# untitled.net
KiCad netlist of a schematic drawn in EAGLE
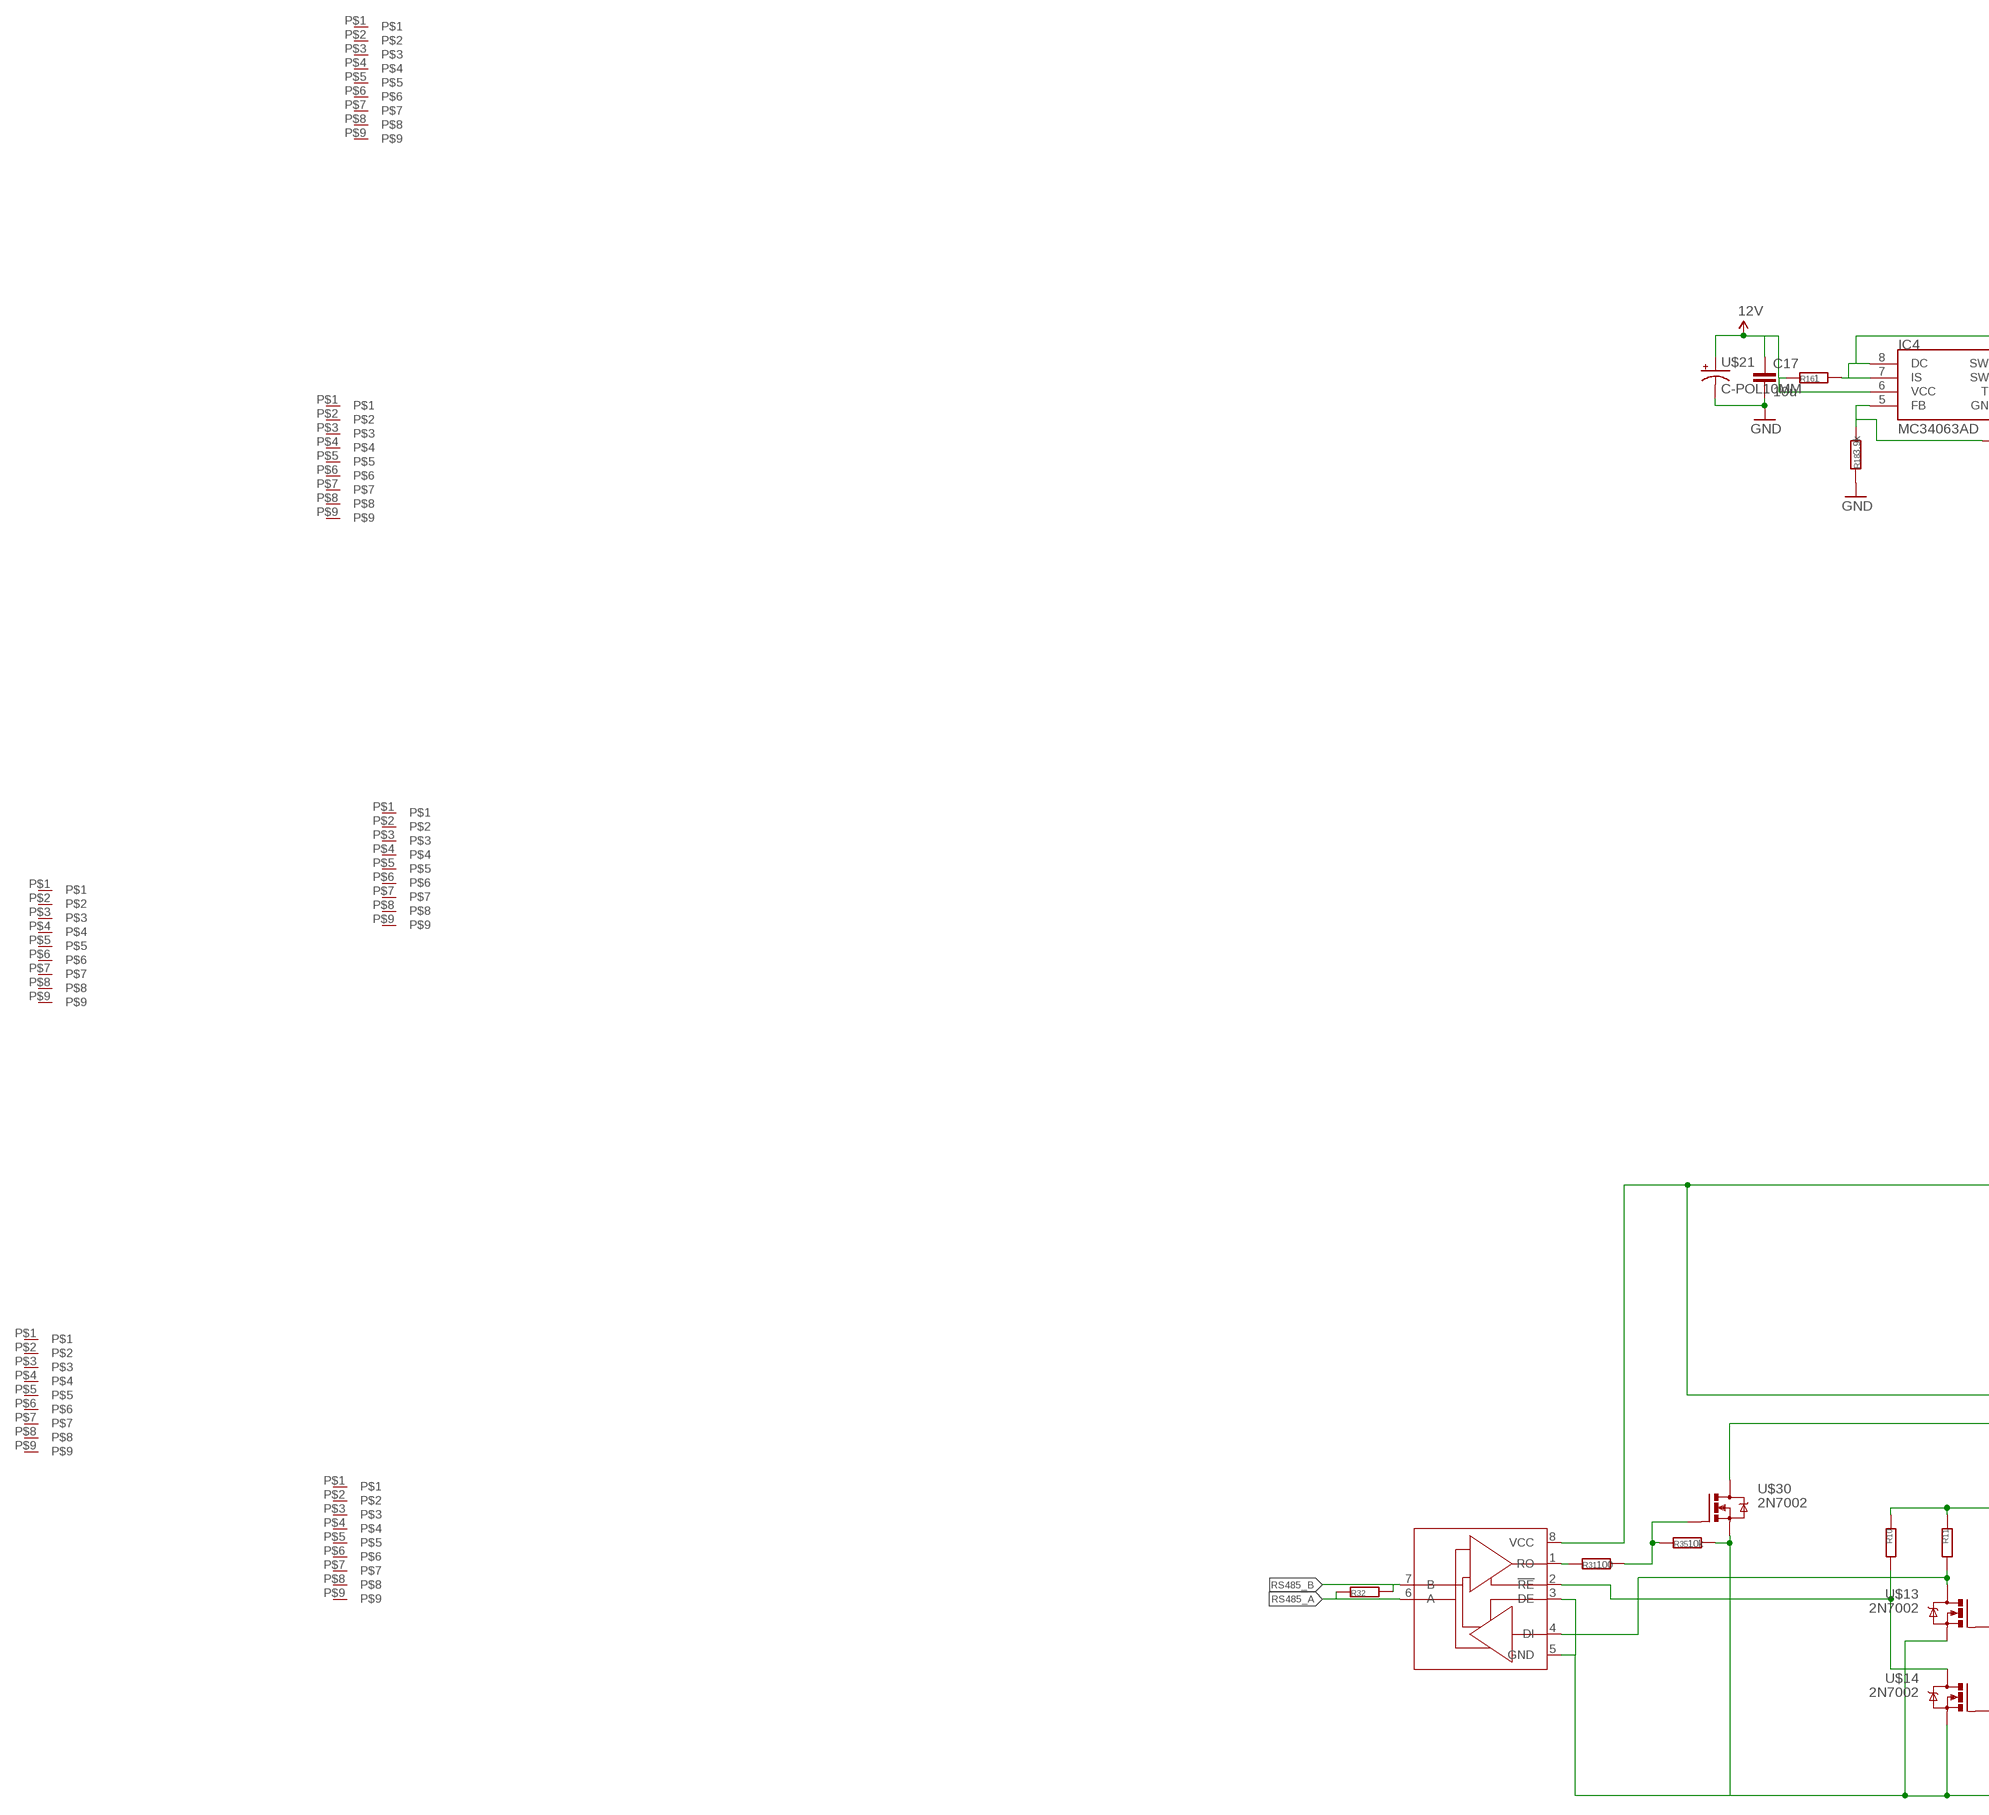
[diagram p0: schematic, sheet 1, part 1 of 2]
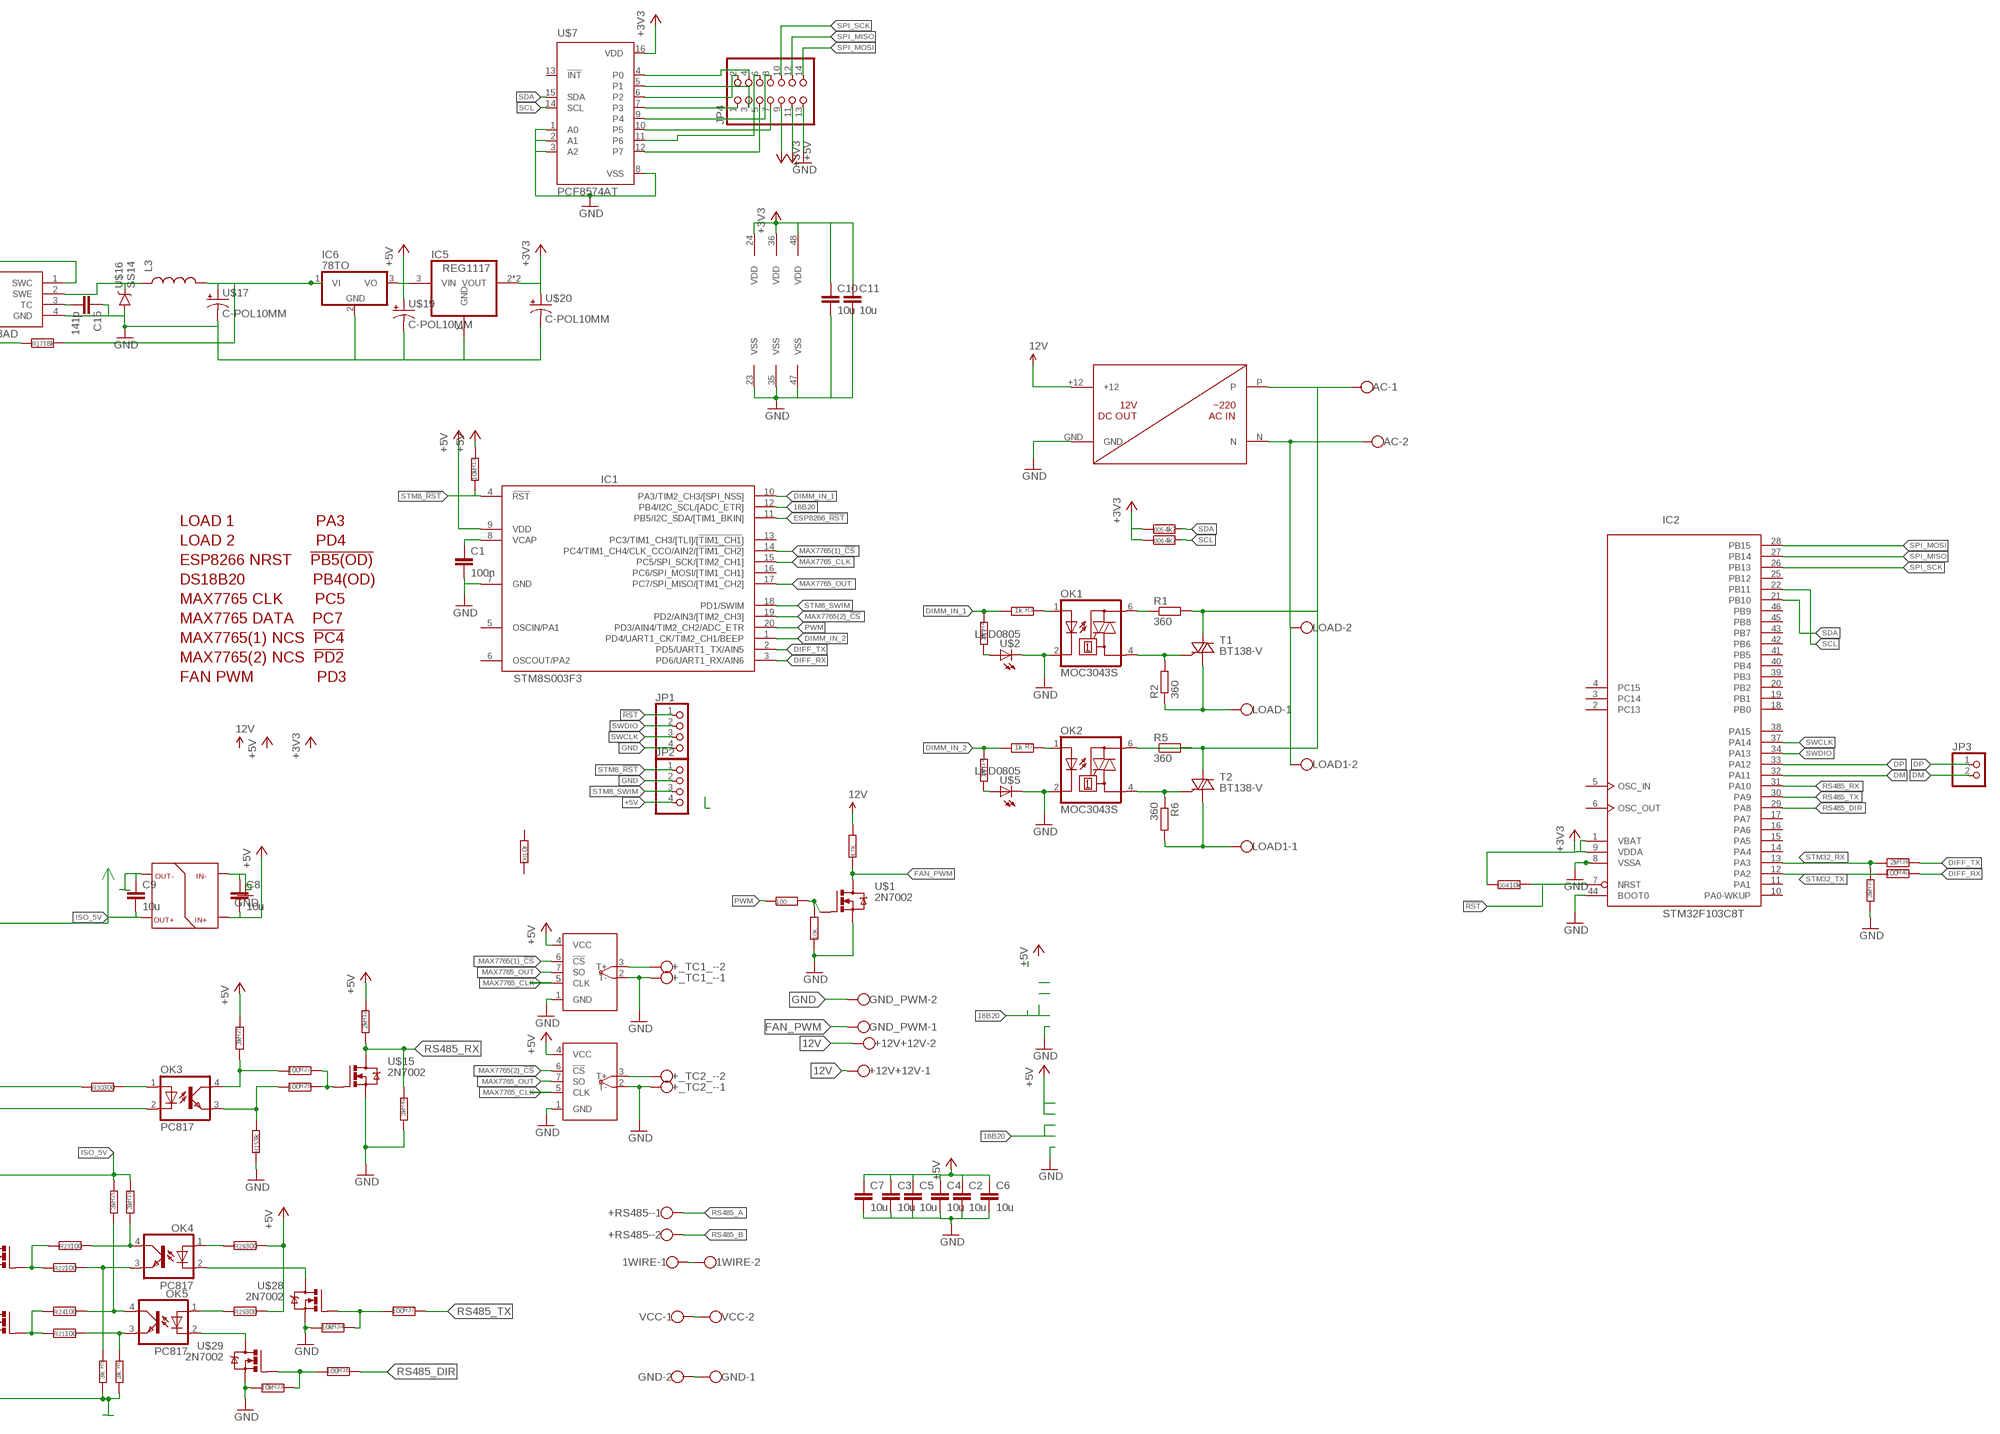
[diagram p1: schematic, sheet 1, part 2 of 2]
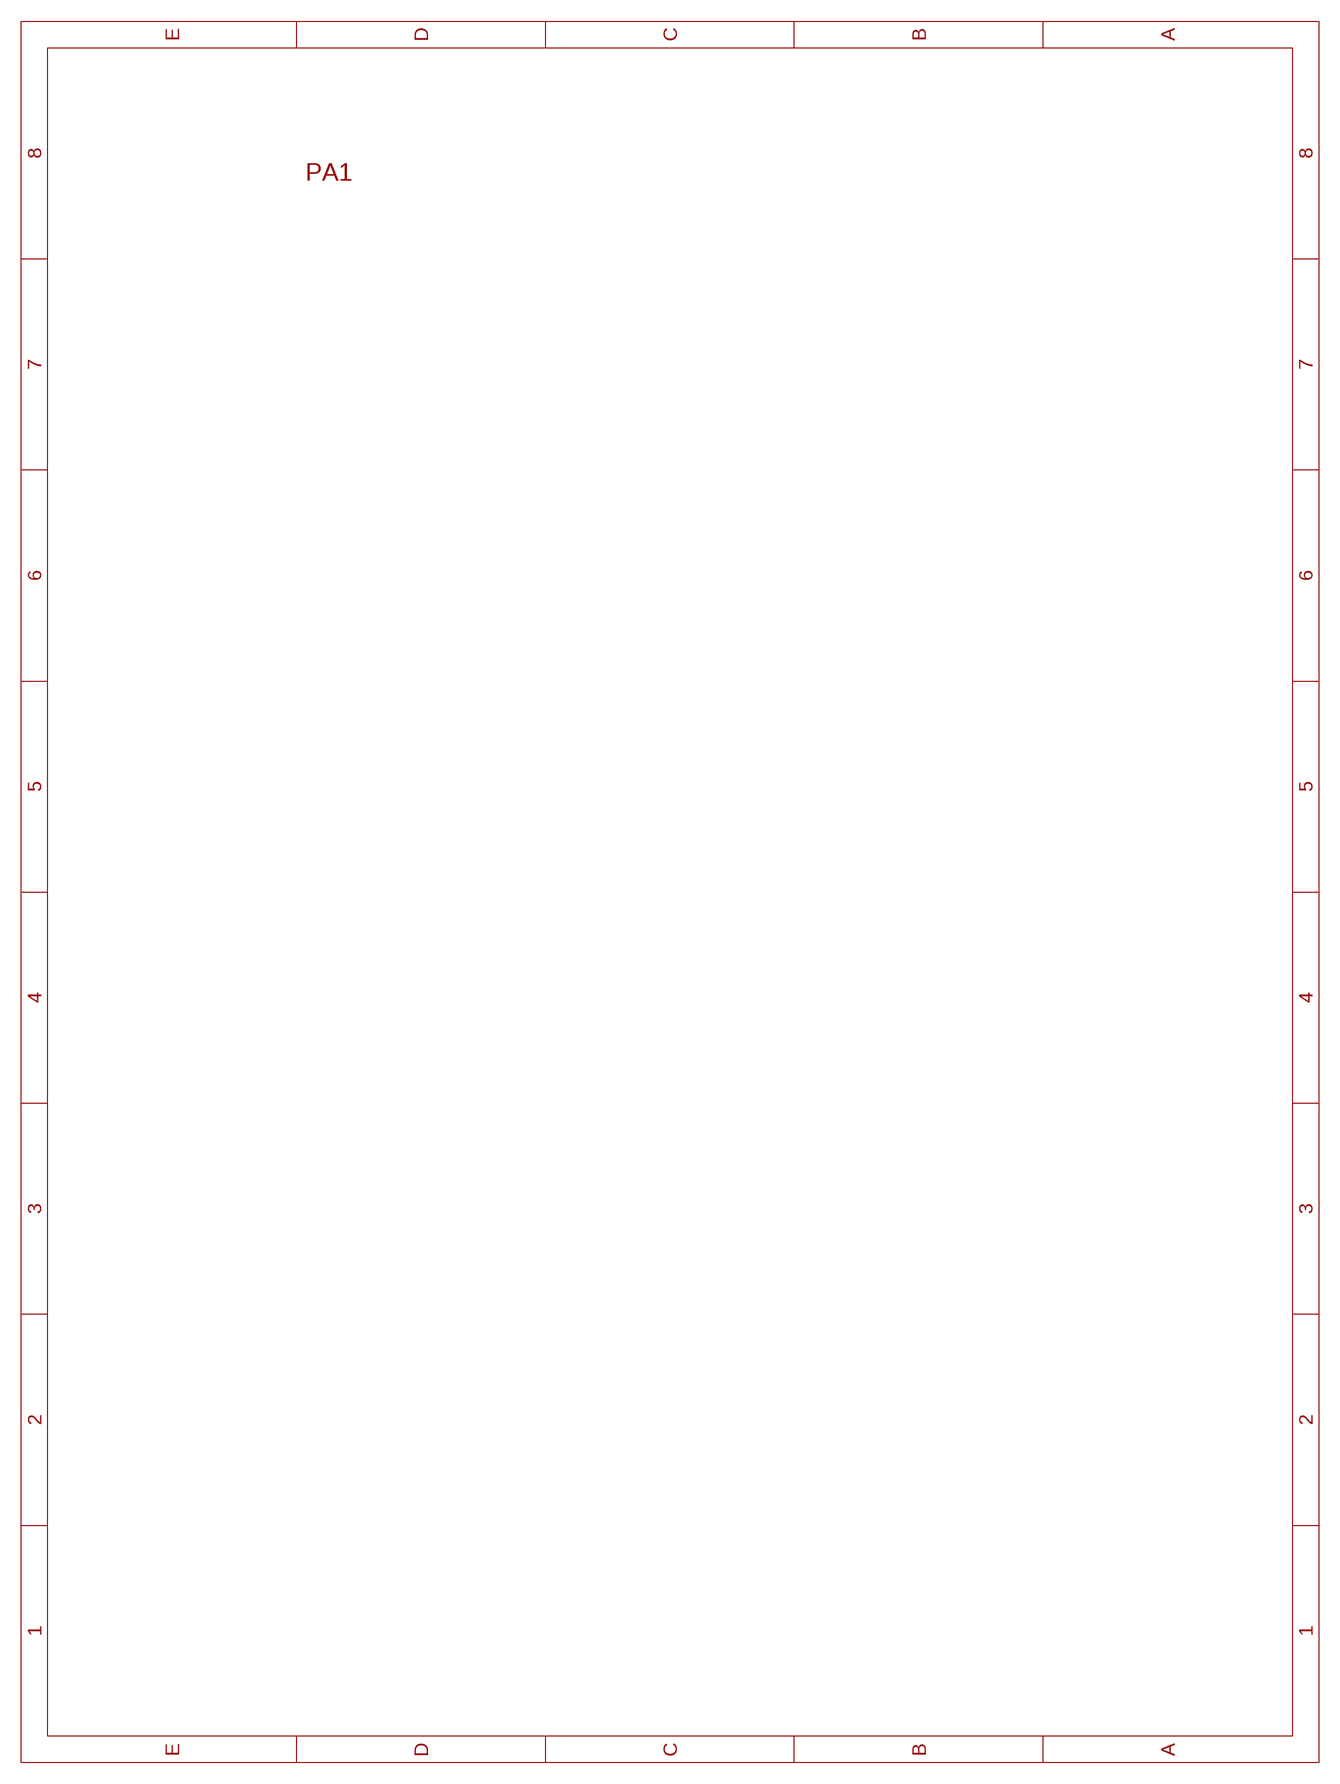
[diagram p2: schematic, sheet 2]

(export (version "E")
  (design (tool "Eeschema 10.0.6"))
  (components
    (comp (ref "+12V+12V")
      (value "W237-102")
      (footprint "eagle-import:W237-102")
      (fields (field (name "MPN") "237-102"))
      (libsource (lib "eagle-import") (part "W237-102"))
    )
    (comp (ref "+RS485-")
      (value "W237-102")
      (footprint "eagle-import:W237-102")
      (fields (field (name "MPN") "237-102"))
      (libsource (lib "eagle-import") (part "W237-102"))
    )
    (comp (ref "+_TC1_-")
      (value "W237-102")
      (footprint "eagle-import:W237-102")
      (fields (field (name "MPN") "237-102"))
      (libsource (lib "eagle-import") (part "W237-102"))
    )
    (comp (ref "+_TC2_-")
      (value "W237-102")
      (footprint "eagle-import:W237-102")
      (fields (field (name "MPN") "237-102"))
      (libsource (lib "eagle-import") (part "W237-102"))
    )
    (comp (ref "001")
      (value "0r")
      (footprint "eagle-import:0603")
      (libsource (lib "eagle-import") (part "R0603"))
    )
    (comp (ref "1WIRE")
      (value "W237-102")
      (footprint "eagle-import:W237-102")
      (fields (field (name "MPN") "237-102"))
      (libsource (lib "eagle-import") (part "W237-102"))
    )
    (comp (ref "004")
      (value "10k")
      (footprint "eagle-import:0603")
      (libsource (lib "eagle-import") (part "R0603"))
    )
    (comp (ref "4.7K")
      (value "R0603")
      (footprint "eagle-import:0603")
      (libsource (lib "eagle-import") (part "R0603"))
    )
    (comp (ref "005")
      (value "4k7")
      (footprint "eagle-import:0603")
      (libsource (lib "eagle-import") (part "R0603"))
    )
    (comp (ref "006")
      (value "4k7")
      (footprint "eagle-import:0603")
      (libsource (lib "eagle-import") (part "R0603"))
    )
    (comp (ref "10K")
      (value "R0603")
      (footprint "eagle-import:0603")
      (libsource (lib "eagle-import") (part "R0603"))
    )
    (comp (ref "100")
      (value "R0603")
      (footprint "eagle-import:0603")
      (libsource (lib "eagle-import") (part "R0603"))
    )
    (comp (ref "AC")
      (value "W237-102")
      (footprint "eagle-import:W237-102")
      (fields (field (name "MPN") "237-102"))
      (libsource (lib "eagle-import") (part "W237-102"))
    )
    (comp (ref "C1")
      (value "100n")
      (footprint "eagle-import:C0603")
      (libsource (lib "eagle-import") (part "CC0603"))
    )
    (comp (ref "C2")
      (value "10u")
      (footprint "eagle-import:C0805")
      (libsource (lib "eagle-import") (part "CC0805"))
    )
    (comp (ref "C3")
      (value "10u")
      (footprint "eagle-import:C0805")
      (libsource (lib "eagle-import") (part "CC0805"))
    )
    (comp (ref "C4")
      (value "10u")
      (footprint "eagle-import:C0805")
      (libsource (lib "eagle-import") (part "CC0805"))
    )
    (comp (ref "C5")
      (value "10u")
      (footprint "eagle-import:C0805")
      (libsource (lib "eagle-import") (part "CC0805"))
    )
    (comp (ref "C6")
      (value "10u")
      (footprint "eagle-import:C0805")
      (libsource (lib "eagle-import") (part "CC0805"))
    )
    (comp (ref "C7")
      (value "10u")
      (footprint "eagle-import:C0805")
      (libsource (lib "eagle-import") (part "CC0805"))
    )
    (comp (ref "C8")
      (value "10u")
      (footprint "eagle-import:C0805")
      (libsource (lib "eagle-import") (part "CC0805"))
    )
    (comp (ref "C9")
      (value "10u")
      (footprint "eagle-import:C0805")
      (libsource (lib "eagle-import") (part "CC0805"))
    )
    (comp (ref "C10")
      (value "10u")
      (footprint "eagle-import:C0603")
      (libsource (lib "eagle-import") (part "CC0603"))
    )
    (comp (ref "C11")
      (value "10u")
      (footprint "eagle-import:C0603")
      (libsource (lib "eagle-import") (part "CC0603"))
    )
    (comp (ref "C15")
      (value "141p")
      (footprint "eagle-import:C0603")
      (libsource (lib "eagle-import") (part "CC0603"))
    )
    (comp (ref "C17")
      (value "10u")
      (footprint "eagle-import:C0805")
      (libsource (lib "eagle-import") (part "CC0805"))
    )
    (comp (ref "GND")
      (value "W237-102")
      (footprint "eagle-import:W237-102")
      (fields (field (name "MPN") "237-102"))
      (libsource (lib "eagle-import") (part "W237-102"))
    )
    (comp (ref "GND_PWM")
      (value "W237-102")
      (footprint "eagle-import:W237-102")
      (fields (field (name "MPN") "237-102"))
      (libsource (lib "eagle-import") (part "W237-102"))
    )
    (comp (ref "IC1")
      (value "STM8S003F3")
      (footprint "eagle-import:TSSOP20")
      (libsource (lib "eagle-import") (part "STM8S003F3"))
    )
    (comp (ref "IC2")
      (value "STM32F103C8T")
      (footprint "eagle-import:LQFP48")
      (libsource (lib "eagle-import") (part "STM32F103CT8"))
    )
    (comp (ref "IC4")
      (value "MC34063AD")
      (footprint "eagle-import:SOIC8")
      (libsource (lib "eagle-import") (part "MC34063AD"))
    )
    (comp (ref "IC5")
      (value "REG1117")
      (footprint "eagle-import:SOT223")
      (libsource (lib "eagle-import") (part "REG1117"))
    )
    (comp (ref "IC6")
      (value "78TO")
      (footprint "eagle-import:D2PACK")
      (libsource (lib "eagle-import") (part "78TO"))
    )
    (comp (ref "JP1")
      (value "PINHD-1X4")
      (footprint "eagle-import:1X04")
      (libsource (lib "eagle-import") (part "PINHD-1X4"))
    )
    (comp (ref "JP2")
      (value "PINHD-1X4")
      (footprint "eagle-import:1X04")
      (libsource (lib "eagle-import") (part "PINHD-1X4"))
    )
    (comp (ref "JP3")
      (value "PINHD-1X02_2.00")
      (footprint "eagle-import:1X02M")
      (libsource (lib "eagle-import") (part "PINHD-1X02_2.00"))
    )
    (comp (ref "JP4")
      (value "PINHD-2X07_2.54-SMD")
      (footprint "eagle-import:2X07SMD")
      (libsource (lib "eagle-import") (part "PINHD-2X07_2.54-SMD"))
    )
    (comp (ref "L3")
      (value "INDUCTORSRU1038")
      (footprint "eagle-import:SRU1038")
      (libsource (lib "eagle-import") (part "INDUCTORSRU1038"))
    )
    (comp (ref "LOAD")
      (value "W237-102")
      (footprint "eagle-import:W237-102")
      (fields (field (name "MPN") "237-102"))
      (libsource (lib "eagle-import") (part "W237-102"))
    )
    (comp (ref "LOAD1")
      (value "W237-102")
      (footprint "eagle-import:W237-102")
      (fields (field (name "MPN") "237-102"))
      (libsource (lib "eagle-import") (part "W237-102"))
    )
    (comp (ref "OK1")
      (value "MOC3043S")
      (footprint "eagle-import:DIL6-SMD")
      (fields (field (name "MF") "FAIRCHILD SEMICONDUCTOR") (field (name "MPN") "MOC3043SM"))
      (libsource (lib "eagle-import") (part "MOC30S43"))
    )
    (comp (ref "OK2")
      (value "MOC3043S")
      (footprint "eagle-import:DIL6-SMD")
      (fields (field (name "MF") "FAIRCHILD SEMICONDUCTOR") (field (name "MPN") "MOC3043SM"))
      (libsource (lib "eagle-import") (part "MOC30S43"))
    )
    (comp (ref "OK3")
      (value "PC817")
      (footprint "eagle-import:DIL4-SMD")
      (libsource (lib "eagle-import") (part "PC817"))
    )
    (comp (ref "OK4")
      (value "PC817")
      (footprint "eagle-import:DIL4-SMD")
      (libsource (lib "eagle-import") (part "PC817"))
    )
    (comp (ref "OK5")
      (value "PC817")
      (footprint "eagle-import:DIL4-SMD")
      (libsource (lib "eagle-import") (part "PC817"))
    )
    (comp (ref "R1")
      (value "360")
      (footprint "eagle-import:0207_5V")
      (libsource (lib "eagle-import") (part "R-EU_0207/5V"))
    )
    (comp (ref "R2")
      (value "360")
      (footprint "eagle-import:0207_5V")
      (libsource (lib "eagle-import") (part "R-EU_0207/5V"))
    )
    (comp (ref "R3")
      (value "1k")
      (footprint "eagle-import:0603")
      (libsource (lib "eagle-import") (part "R0603"))
    )
    (comp (ref "R4")
      (value "1k")
      (footprint "eagle-import:0603")
      (libsource (lib "eagle-import") (part "R0603"))
    )
    (comp (ref "R5")
      (value "360")
      (footprint "eagle-import:0207_5V")
      (libsource (lib "eagle-import") (part "R-EU_0207/5V"))
    )
    (comp (ref "R6")
      (value "360")
      (footprint "eagle-import:0207_5V")
      (libsource (lib "eagle-import") (part "R-EU_0207/5V"))
    )
    (comp (ref "R7")
      (value "1k")
      (footprint "eagle-import:0603")
      (libsource (lib "eagle-import") (part "R0603"))
    )
    (comp (ref "R8")
      (value "3k")
      (footprint "eagle-import:0603")
      (libsource (lib "eagle-import") (part "R0603"))
    )
    (comp (ref "R9")
      (value "3k")
      (footprint "eagle-import:0603")
      (libsource (lib "eagle-import") (part "R0603"))
    )
    (comp (ref "R10")
      (value "R0603")
      (footprint "eagle-import:0603")
      (libsource (lib "eagle-import") (part "R0603"))
    )
    (comp (ref "R11")
      (value "R0603")
      (footprint "eagle-import:0603")
      (libsource (lib "eagle-import") (part "R0603"))
    )
    (comp (ref "R12")
      (value "2k")
      (footprint "eagle-import:0603")
      (libsource (lib "eagle-import") (part "R0603"))
    )
    (comp (ref "R13")
      (value "10k")
      (footprint "eagle-import:0603")
      (libsource (lib "eagle-import") (part "R0603"))
    )
    (comp (ref "R14")
      (value "1k")
      (footprint "eagle-import:0603")
      (libsource (lib "eagle-import") (part "R0603"))
    )
    (comp (ref "R15")
      (value "3k")
      (footprint "eagle-import:0603")
      (libsource (lib "eagle-import") (part "R0603"))
    )
    (comp (ref "R16")
      (value "1")
      (footprint "eagle-import:R0805")
      (libsource (lib "eagle-import") (part "R0805"))
    )
    (comp (ref "R17")
      (value "18k")
      (footprint "eagle-import:0603")
      (libsource (lib "eagle-import") (part "R0603"))
    )
    (comp (ref "R18")
      (value "3.9k")
      (footprint "eagle-import:0603")
      (libsource (lib "eagle-import") (part "R0603"))
    )
    (comp (ref "R19")
      (value "3k")
      (footprint "eagle-import:0603")
      (libsource (lib "eagle-import") (part "R0603"))
    )
    (comp (ref "R20")
      (value "3k")
      (footprint "eagle-import:0603")
      (libsource (lib "eagle-import") (part "R0603"))
    )
    (comp (ref "R21")
      (value "100")
      (footprint "eagle-import:0603")
      (libsource (lib "eagle-import") (part "R0603"))
    )
    (comp (ref "R22")
      (value "100")
      (footprint "eagle-import:0603")
      (libsource (lib "eagle-import") (part "R0603"))
    )
    (comp (ref "R23")
      (value "100")
      (footprint "eagle-import:0603")
      (libsource (lib "eagle-import") (part "R0603"))
    )
    (comp (ref "R24")
      (value "100")
      (footprint "eagle-import:0603")
      (libsource (lib "eagle-import") (part "R0603"))
    )
    (comp (ref "R25")
      (value "3k")
      (footprint "eagle-import:0603")
      (libsource (lib "eagle-import") (part "R0603"))
    )
    (comp (ref "R26")
      (value "100")
      (footprint "eagle-import:0603")
      (libsource (lib "eagle-import") (part "R0603"))
    )
    (comp (ref "R27")
      (value "100")
      (footprint "eagle-import:0603")
      (libsource (lib "eagle-import") (part "R0603"))
    )
    (comp (ref "R28")
      (value "300")
      (footprint "eagle-import:0603")
      (libsource (lib "eagle-import") (part "R0603"))
    )
    (comp (ref "R29")
      (value "300")
      (footprint "eagle-import:0603")
      (libsource (lib "eagle-import") (part "R0603"))
    )
    (comp (ref "R30")
      (value "300")
      (footprint "eagle-import:0603")
      (libsource (lib "eagle-import") (part "R0603"))
    )
    (comp (ref "R31")
      (value "100")
      (footprint "eagle-import:0603")
      (libsource (lib "eagle-import") (part "R0603"))
    )
    (comp (ref "R32")
      (value "R0805")
      (footprint "eagle-import:R0805")
      (libsource (lib "eagle-import") (part "R0805"))
    )
    (comp (ref "R33")
      (value "10k")
      (footprint "eagle-import:0603")
      (libsource (lib "eagle-import") (part "R0603"))
    )
    (comp (ref "R34")
      (value "10k")
      (footprint "eagle-import:0603")
      (libsource (lib "eagle-import") (part "R0603"))
    )
    (comp (ref "R35")
      (value "10k")
      (footprint "eagle-import:0603")
      (libsource (lib "eagle-import") (part "R0603"))
    )
    (comp (ref "R36")
      (value "100")
      (footprint "eagle-import:0603")
      (libsource (lib "eagle-import") (part "R0603"))
    )
    (comp (ref "R37")
      (value "100")
      (footprint "eagle-import:0603")
      (libsource (lib "eagle-import") (part "R0603"))
    )
    (comp (ref "R38")
      (value "2k")
      (footprint "eagle-import:0603")
      (libsource (lib "eagle-import") (part "R0603"))
    )
    (comp (ref "R39")
      (value "3k")
      (footprint "eagle-import:0603")
      (libsource (lib "eagle-import") (part "R0603"))
    )
    (comp (ref "R40")
      (value "100")
      (footprint "eagle-import:0603")
      (libsource (lib "eagle-import") (part "R0603"))
    )
    (comp (ref "R41")
      (value "3k")
      (footprint "eagle-import:0603")
      (libsource (lib "eagle-import") (part "R0603"))
    )
    (comp (ref "T1")
      (value "BT138-V")
      (footprint "eagle-import:TO220BV")
      (libsource (lib "eagle-import") (part "BT138-V"))
    )
    (comp (ref "T2")
      (value "BT138-V")
      (footprint "eagle-import:TO220BV")
      (libsource (lib "eagle-import") (part "BT138-V"))
    )
    (comp (ref "U$1")
      (value "2N7002")
      (footprint "eagle-import:SOT23")
      (libsource (lib "eagle-import") (part "2N7002"))
    )
    (comp (ref "U$2")
      (value "LED0805")
      (footprint "eagle-import:0805-LED")
      (libsource (lib "eagle-import") (part "LED0805"))
    )
    (comp (ref "U$3")
      (value "MAX6675")
      (footprint "eagle-import:SO08")
      (libsource (lib "eagle-import") (part "MAX6675"))
    )
    (comp (ref "U$4")
      (value "ADM1485")
      (footprint "eagle-import:SO08")
      (libsource (lib "eagle-import") (part "ADM1485"))
    )
    (comp (ref "U$5")
      (value "LED0805")
      (footprint "eagle-import:0805-LED")
      (libsource (lib "eagle-import") (part "LED0805"))
    )
    (comp (ref "U$6")
      (value "MAX6675")
      (footprint "eagle-import:SO08")
      (libsource (lib "eagle-import") (part "MAX6675"))
    )
    (comp (ref "U$7")
      (value "PCF8574AT")
      (footprint "eagle-import:SO16L")
      (libsource (lib "eagle-import") (part "PCF8574AT"))
    )
    (comp (ref "U$8")
      (value "AC-DC")
      (footprint "eagle-import:ACDC12(1)")
      (libsource (lib "eagle-import") (part "AC-DC"))
    )
    (comp (ref "U$12")
      (value "DCDC5050")
      (footprint "eagle-import:DCDC_0505")
      (libsource (lib "eagle-import") (part "DCDC5050"))
    )
    (comp (ref "U$13")
      (value "2N7002")
      (footprint "eagle-import:SOT23")
      (libsource (lib "eagle-import") (part "2N7002"))
    )
    (comp (ref "U$14")
      (value "2N7002")
      (footprint "eagle-import:SOT23")
      (libsource (lib "eagle-import") (part "2N7002"))
    )
    (comp (ref "U$15")
      (value "2N7002")
      (footprint "eagle-import:SOT23")
      (libsource (lib "eagle-import") (part "2N7002"))
    )
    (comp (ref "U$16")
      (value "SS14")
      (footprint "eagle-import:SMA-DIODE")
      (libsource (lib "eagle-import") (part "SS14"))
    )
    (comp (ref "U$17")
      (value "C-POL10MM")
      (footprint "eagle-import:PCAP10")
      (libsource (lib "eagle-import") (part "C-POL10MM"))
    )
    (comp (ref "U$19")
      (value "C-POL10MM")
      (footprint "eagle-import:PCAP10")
      (libsource (lib "eagle-import") (part "C-POL10MM"))
    )
    (comp (ref "U$20")
      (value "C-POL10MM")
      (footprint "eagle-import:PCAP10")
      (libsource (lib "eagle-import") (part "C-POL10MM"))
    )
    (comp (ref "U$21")
      (value "C-POL10MM")
      (footprint "eagle-import:PCAP10")
      (libsource (lib "eagle-import") (part "C-POL10MM"))
    )
    (comp (ref "U$22")
      (value "D9MG")
      (footprint "eagle-import:D9MG")
      (libsource (lib "eagle-import") (part "D9MG"))
    )
    (comp (ref "U$23")
      (value "D9MG")
      (footprint "eagle-import:D9MG")
      (libsource (lib "eagle-import") (part "D9MG"))
    )
    (comp (ref "U$24")
      (value "D9MG")
      (footprint "eagle-import:D9MG")
      (libsource (lib "eagle-import") (part "D9MG"))
    )
    (comp (ref "U$25")
      (value "D9MG")
      (footprint "eagle-import:D9MG")
      (libsource (lib "eagle-import") (part "D9MG"))
    )
    (comp (ref "U$26")
      (value "D9MG")
      (footprint "eagle-import:D9MG")
      (libsource (lib "eagle-import") (part "D9MG"))
    )
    (comp (ref "U$27")
      (value "D9MG")
      (footprint "eagle-import:D9MG")
      (libsource (lib "eagle-import") (part "D9MG"))
    )
    (comp (ref "U$28")
      (value "2N7002")
      (footprint "eagle-import:SOT23")
      (libsource (lib "eagle-import") (part "2N7002"))
    )
    (comp (ref "U$29")
      (value "2N7002")
      (footprint "eagle-import:SOT23")
      (libsource (lib "eagle-import") (part "2N7002"))
    )
    (comp (ref "U$30")
      (value "2N7002")
      (footprint "eagle-import:SOT23")
      (libsource (lib "eagle-import") (part "2N7002"))
    )
    (comp (ref "VCC")
      (value "W237-102")
      (footprint "eagle-import:W237-102")
      (fields (field (name "MPN") "237-102"))
      (libsource (lib "eagle-import") (part "W237-102"))
    )
  )
  (nets
    (net (code "1") (name "+3V3") (class "Default")
      (node (ref "004") (pin "1") (pinfunction "1_1") (pintype "passive"))
      (node (ref "005") (pin "1") (pinfunction "1_1") (pintype "passive"))
      (node (ref "006") (pin "1") (pinfunction "1_1") (pintype "passive"))
      (node (ref "C10") (pin "1") (pinfunction "1_1") (pintype "passive"))
      (node (ref "C11") (pin "1") (pinfunction "1_1") (pintype "passive"))
      (node (ref "IC2") (pin "1") (pinfunction "VBAT_1") (pintype "power_in"))
      (node (ref "IC2") (pin "24") (pinfunction "VDD_24") (pintype "power_in"))
      (node (ref "IC2") (pin "36") (pinfunction "VDD_36") (pintype "power_in"))
      (node (ref "IC2") (pin "48") (pinfunction "VDD_48") (pintype "power_in"))
      (node (ref "IC2") (pin "9") (pinfunction "VDDA_9") (pintype "power_in"))
      (node (ref "IC5") (pin "2") (pinfunction "VOUT_2") (pintype "output"))
      (node (ref "IC5") (pin "4") (pinfunction "VOUT_4") (pintype "output"))
      (node (ref "JP4") (pin "9") (pinfunction "9_9") (pintype "passive"))
      (node (ref "U$20") (pin "P$1") (pinfunction "+_P$1") (pintype "passive"))
      (node (ref "U$7") (pin "16") (pinfunction "VDD_16") (pintype "power_in"))
    )
    (net (code "2") (name "+5V") (class "Default")
      (node (ref "C2") (pin "1") (pinfunction "1_1") (pintype "passive"))
      (node (ref "C3") (pin "1") (pinfunction "1_1") (pintype "passive"))
      (node (ref "C4") (pin "1") (pinfunction "1_1") (pintype "passive"))
      (node (ref "C5") (pin "1") (pinfunction "1_1") (pintype "passive"))
      (node (ref "C6") (pin "1") (pinfunction "1_1") (pintype "passive"))
      (node (ref "C7") (pin "1") (pinfunction "1_1") (pintype "passive"))
      (node (ref "C8") (pin "2") (pinfunction "2_2") (pintype "passive"))
      (node (ref "IC1") (pin "9") (pinfunction "VDD_9") (pintype "power_in"))
      (node (ref "IC5") (pin "3") (pinfunction "VIN_3") (pintype "input"))
      (node (ref "IC6") (pin "3") (pinfunction "VO_3") (pintype "passive"))
      (node (ref "JP2") (pin "4") (pinfunction "4_4") (pintype "passive"))
      (node (ref "JP4") (pin "11") (pinfunction "11_11") (pintype "passive"))
      (node (ref "R12") (pin "1") (pinfunction "1_1") (pintype "passive"))
      (node (ref "R13") (pin "1") (pinfunction "1_1") (pintype "passive"))
      (node (ref "R25") (pin "1") (pinfunction "1_1") (pintype "passive"))
      (node (ref "R28") (pin "2") (pinfunction "2_2") (pintype "passive"))
      (node (ref "R29") (pin "2") (pinfunction "2_2") (pintype "passive"))
      (node (ref "U$12") (pin "P$2") (pinfunction "IN+_P$2") (pintype "bidirectional"))
      (node (ref "U$19") (pin "P$1") (pinfunction "+_P$1") (pintype "passive"))
      (node (ref "U$3") (pin "4") (pinfunction "VCC_4") (pintype "bidirectional"))
      (node (ref "U$6") (pin "4") (pinfunction "VCC_4") (pintype "bidirectional"))
      (node (ref "VCC") (pin "1") (pinfunction "KL_1") (pintype "passive"))
      (node (ref "VCC") (pin "2") (pinfunction "KL_2") (pintype "passive"))
    )
    (net (code "3") (name "12V") (class "Default")
      (node (ref "+12V+12V") (pin "1") (pinfunction "KL_1") (pintype "passive"))
      (node (ref "+12V+12V") (pin "2") (pinfunction "KL_2") (pintype "passive"))
      (node (ref "4.7K") (pin "2") (pinfunction "2_2") (pintype "passive"))
      (node (ref "C17") (pin "1") (pinfunction "1_1") (pintype "passive"))
      (node (ref "IC4") (pin "6") (pinfunction "VCC_6") (pintype "passive"))
      (node (ref "R16") (pin "1") (pinfunction "1_1") (pintype "passive"))
      (node (ref "U$21") (pin "P$1") (pinfunction "+_P$1") (pintype "passive"))
      (node (ref "U$8") (pin "+12") (pinfunction "+12_+12") (pintype "bidirectional"))
    )
    (net (code "4") (name "18B20") (class "Default")
      (node (ref "1WIRE") (pin "1") (pinfunction "KL_1") (pintype "passive"))
      (node (ref "1WIRE") (pin "2") (pinfunction "KL_2") (pintype "passive"))
      (node (ref "IC1") (pin "12") (pinfunction "PB4/I2C_SCL/[ADC_ETR]_12") (pintype "bidirectional"))
    )
    (net (code "5") (name "DIFF_RX") (class "Default")
      (node (ref "IC1") (pin "3") (pinfunction "PD6/UART1_RX/AIN6_3") (pintype "bidirectional"))
      (node (ref "R40") (pin "1") (pinfunction "1_1") (pintype "passive"))
    )
    (net (code "6") (name "DIFF_TX") (class "Default")
      (node (ref "IC1") (pin "2") (pinfunction "PD5/UART1_TX/AIN5_2") (pintype "bidirectional"))
      (node (ref "R38") (pin "1") (pinfunction "1_1") (pintype "passive"))
    )
    (net (code "7") (name "DIMM_IN_1") (class "Default")
      (node (ref "IC1") (pin "10") (pinfunction "PA3/TIM2_CH3/[SPI_NSS]_10") (pintype "bidirectional"))
      (node (ref "R3") (pin "2") (pinfunction "2_2") (pintype "passive"))
      (node (ref "R4") (pin "1") (pinfunction "1_1") (pintype "passive"))
    )
    (net (code "8") (name "DIMM_IN_2") (class "Default")
      (node (ref "IC1") (pin "1") (pinfunction "PD4/UART1_CK/TIM2_CH1/BEEP_1") (pintype "bidirectional"))
      (node (ref "R14") (pin "1") (pinfunction "1_1") (pintype "passive"))
      (node (ref "R7") (pin "2") (pinfunction "2_2") (pintype "passive"))
    )
    (net (code "9") (name "DM") (class "Default")
      (node (ref "IC2") (pin "32") (pinfunction "PA11_32") (pintype "bidirectional"))
      (node (ref "JP3") (pin "2") (pinfunction "2_2") (pintype "passive"))
    )
    (net (code "10") (name "DP") (class "Default")
      (node (ref "IC2") (pin "33") (pinfunction "PA12_33") (pintype "bidirectional"))
      (node (ref "JP3") (pin "1") (pinfunction "1_1") (pintype "passive"))
    )
    (net (code "11") (name "ESP8266_~{RST}") (class "Default")
      (node (ref "IC1") (pin "11") (pinfunction "PB5/I2C_SDA/[TIM1_BKIN]_11") (pintype "bidirectional"))
    )
    (net (code "12") (name "FAN_PWM") (class "Default")
      (node (ref "4.7K") (pin "1") (pinfunction "1_1") (pintype "passive"))
      (node (ref "GND_PWM") (pin "1") (pinfunction "KL_1") (pintype "passive"))
      (node (ref "U$1") (pin "3") (pinfunction "D_3") (pintype "passive"))
    )
    (net (code "13") (name "GND") (class "Default")
      (node (ref "+_TC1_-") (pin "1") (pinfunction "KL_1") (pintype "passive"))
      (node (ref "+_TC2_-") (pin "1") (pinfunction "KL_1") (pintype "passive"))
      (node (ref "10K") (pin "1") (pinfunction "1_1") (pintype "passive"))
      (node (ref "C1") (pin "2") (pinfunction "2_2") (pintype "passive"))
      (node (ref "C10") (pin "2") (pinfunction "2_2") (pintype "passive"))
      (node (ref "C11") (pin "2") (pinfunction "2_2") (pintype "passive"))
      (node (ref "C15") (pin "1") (pinfunction "1_1") (pintype "passive"))
      (node (ref "C17") (pin "2") (pinfunction "2_2") (pintype "passive"))
      (node (ref "C2") (pin "2") (pinfunction "2_2") (pintype "passive"))
      (node (ref "C3") (pin "2") (pinfunction "2_2") (pintype "passive"))
      (node (ref "C4") (pin "2") (pinfunction "2_2") (pintype "passive"))
      (node (ref "C5") (pin "2") (pinfunction "2_2") (pintype "passive"))
      (node (ref "C6") (pin "2") (pinfunction "2_2") (pintype "passive"))
      (node (ref "C7") (pin "2") (pinfunction "2_2") (pintype "passive"))
      (node (ref "C8") (pin "1") (pinfunction "1_1") (pintype "passive"))
      (node (ref "GND") (pin "1") (pinfunction "KL_1") (pintype "passive"))
      (node (ref "GND") (pin "2") (pinfunction "KL_2") (pintype "passive"))
      (node (ref "GND_PWM") (pin "2") (pinfunction "KL_2") (pintype "passive"))
      (node (ref "IC1") (pin "7") (pinfunction "GND_7") (pintype "power_in"))
      (node (ref "IC2") (pin "23") (pinfunction "VSS_23") (pintype "power_in"))
      (node (ref "IC2") (pin "35") (pinfunction "VSS_35") (pintype "power_in"))
      (node (ref "IC2") (pin "44") (pinfunction "BOOT0_44") (pintype "input"))
      (node (ref "IC2") (pin "47") (pinfunction "VSS_47") (pintype "power_in"))
      (node (ref "IC2") (pin "8") (pinfunction "VSSA_8") (pintype "power_in"))
      (node (ref "IC4") (pin "4") (pinfunction "GND_4") (pintype "passive"))
      (node (ref "IC5") (pin "1") (pinfunction "GND_1") (pintype "power_in"))
      (node (ref "IC6") (pin "2") (pinfunction "GND_2") (pintype "passive"))
      (node (ref "JP1") (pin "4") (pinfunction "4_4") (pintype "passive"))
      (node (ref "JP2") (pin "2") (pinfunction "2_2") (pintype "passive"))
      (node (ref "JP4") (pin "13") (pinfunction "13_13") (pintype "passive"))
      (node (ref "OK1") (pin "2") (pinfunction "C_2") (pintype "passive"))
      (node (ref "OK2") (pin "2") (pinfunction "C_2") (pintype "passive"))
      (node (ref "R15") (pin "1") (pinfunction "1_1") (pintype "passive"))
      (node (ref "R18") (pin "1") (pinfunction "1_1") (pintype "passive"))
      (node (ref "R33") (pin "2") (pinfunction "2_2") (pintype "passive"))
      (node (ref "R34") (pin "2") (pinfunction "2_2") (pintype "passive"))
      (node (ref "R39") (pin "2") (pinfunction "2_2") (pintype "passive"))
      (node (ref "R41") (pin "2") (pinfunction "2_2") (pintype "passive"))
      (node (ref "U$1") (pin "2") (pinfunction "S_2") (pintype "passive"))
      (node (ref "U$12") (pin "P$1") (pinfunction "IN-_P$1") (pintype "bidirectional"))
      (node (ref "U$15") (pin "2") (pinfunction "S_2") (pintype "passive"))
      (node (ref "U$16") (pin "A") (pinfunction "A_A") (pintype "passive"))
      (node (ref "U$17") (pin "P$2") (pinfunction "-_P$2") (pintype "passive"))
      (node (ref "U$19") (pin "P$2") (pinfunction "-_P$2") (pintype "passive"))
      (node (ref "U$2") (pin "C") (pinfunction "C_C") (pintype "passive"))
      (node (ref "U$20") (pin "P$2") (pinfunction "-_P$2") (pintype "passive"))
      (node (ref "U$21") (pin "P$2") (pinfunction "-_P$2") (pintype "passive"))
      (node (ref "U$28") (pin "2") (pinfunction "S_2") (pintype "passive"))
      (node (ref "U$29") (pin "2") (pinfunction "S_2") (pintype "passive"))
      (node (ref "U$3") (pin "1") (pinfunction "GND_1") (pintype "bidirectional"))
      (node (ref "U$3") (pin "2") (pinfunction "T-_2") (pintype "bidirectional"))
      (node (ref "U$5") (pin "C") (pinfunction "C_C") (pintype "passive"))
      (node (ref "U$6") (pin "1") (pinfunction "GND_1") (pintype "bidirectional"))
      (node (ref "U$6") (pin "2") (pinfunction "T-_2") (pintype "bidirectional"))
      (node (ref "U$7") (pin "1") (pinfunction "A0_1") (pintype "input"))
      (node (ref "U$7") (pin "2") (pinfunction "A1_2") (pintype "input"))
      (node (ref "U$7") (pin "3") (pinfunction "A2_3") (pintype "input"))
      (node (ref "U$7") (pin "8") (pinfunction "VSS_8") (pintype "power_in"))
      (node (ref "U$8") (pin "GND") (pinfunction "GND_GND") (pintype "bidirectional"))
    )
    (net (code "14") (name "ISO_5V") (class "Default")
      (node (ref "C9") (pin "2") (pinfunction "2_2") (pintype "passive"))
      (node (ref "R10") (pin "1") (pinfunction "1_1") (pintype "passive"))
      (node (ref "R11") (pin "1") (pinfunction "1_1") (pintype "passive"))
      (node (ref "R19") (pin "1") (pinfunction "1_1") (pintype "passive"))
      (node (ref "R20") (pin "1") (pinfunction "1_1") (pintype "passive"))
      (node (ref "R30") (pin "1") (pinfunction "1_1") (pintype "passive"))
      (node (ref "U$12") (pin "P$5") (pinfunction "OUT+_P$5") (pintype "bidirectional"))
      (node (ref "U$4") (pin "8") (pinfunction "VCC_8") (pintype "bidirectional"))
    )
    (net (code "15") (name "ISO_GND") (class "Default")
      (node (ref "C9") (pin "1") (pinfunction "1_1") (pintype "passive"))
      (node (ref "R35") (pin "2") (pinfunction "2_2") (pintype "passive"))
      (node (ref "R8") (pin "2") (pinfunction "2_2") (pintype "passive"))
      (node (ref "R9") (pin "2") (pinfunction "2_2") (pintype "passive"))
      (node (ref "U$12") (pin "P$4") (pinfunction "OUT-_P$4") (pintype "bidirectional"))
      (node (ref "U$13") (pin "2") (pinfunction "S_2") (pintype "passive"))
      (node (ref "U$14") (pin "2") (pinfunction "S_2") (pintype "passive"))
      (node (ref "U$30") (pin "2") (pinfunction "S_2") (pintype "passive"))
      (node (ref "U$4") (pin "3") (pinfunction "DE_3") (pintype "bidirectional"))
      (node (ref "U$4") (pin "5") (pinfunction "GND_5") (pintype "bidirectional"))
    )
    (net (code "16") (name "MAX7765(1)_~{CS}") (class "Default")
      (node (ref "IC1") (pin "14") (pinfunction "PC4/TIM1_CH4/CLK_CCO/AIN2/[~{TIM1_CH2}]_14") (pintype "bidirectional"))
      (node (ref "U$3") (pin "6") (pinfunction "~{CS}_6") (pintype "bidirectional"))
    )
    (net (code "17") (name "MAX7765(2)_~{CS}") (class "Default")
      (node (ref "IC1") (pin "19") (pinfunction "PD2/AIN3/[TIM2_CH3]_19") (pintype "bidirectional"))
      (node (ref "U$6") (pin "6") (pinfunction "~{CS}_6") (pintype "bidirectional"))
    )
    (net (code "18") (name "MAX7765_CLK") (class "Default")
      (node (ref "IC1") (pin "15") (pinfunction "PC5/SPI_SCK/[TIM2_CH1]_15") (pintype "bidirectional"))
      (node (ref "U$3") (pin "5") (pinfunction "CLK_5") (pintype "bidirectional"))
      (node (ref "U$6") (pin "5") (pinfunction "CLK_5") (pintype "bidirectional"))
    )
    (net (code "19") (name "MAX7765_OUT") (class "Default")
      (node (ref "IC1") (pin "17") (pinfunction "PC7/SPI_MISO/[TIM1_CH2]_17") (pintype "bidirectional"))
      (node (ref "U$3") (pin "7") (pinfunction "SO_7") (pintype "bidirectional"))
      (node (ref "U$6") (pin "7") (pinfunction "SO_7") (pintype "bidirectional"))
    )
    (net (code "20") (name "Net-(+_TC1_-B-KL)") (class "Default")
      (node (ref "+_TC1_-") (pin "2") (pinfunction "KL_2") (pintype "passive"))
      (node (ref "U$3") (pin "3") (pinfunction "T+_3") (pintype "bidirectional"))
    )
    (net (code "21") (name "Net-(+_TC2_-B-KL)") (class "Default")
      (node (ref "+_TC2_-") (pin "2") (pinfunction "KL_2") (pintype "passive"))
      (node (ref "U$6") (pin "3") (pinfunction "T+_3") (pintype "bidirectional"))
    )
    (net (code "22") (name "Net-(ACA-KL)") (class "Default")
      (node (ref "AC") (pin "1") (pinfunction "KL_1") (pintype "passive"))
      (node (ref "R1") (pin "2") (pinfunction "2_2") (pintype "passive"))
      (node (ref "R5") (pin "1") (pinfunction "1_1") (pintype "passive"))
      (node (ref "T1") (pin "T2") (pinfunction "A2_T2") (pintype "passive"))
      (node (ref "T2") (pin "T2") (pinfunction "A2_T2") (pintype "passive"))
      (node (ref "U$8") (pin "P") (pinfunction "P_P") (pintype "bidirectional"))
    )
    (net (code "23") (name "Net-(ACB-KL)") (class "Default")
      (node (ref "AC") (pin "2") (pinfunction "KL_2") (pintype "passive"))
      (node (ref "LOAD") (pin "2") (pinfunction "KL_2") (pintype "passive"))
      (node (ref "LOAD1") (pin "2") (pinfunction "KL_2") (pintype "passive"))
      (node (ref "U$8") (pin "N") (pinfunction "N_N") (pintype "bidirectional"))
    )
    (net (code "24") (name "Net-(IC1-VCAP)") (class "Default")
      (node (ref "C1") (pin "1") (pinfunction "1_1") (pintype "passive"))
      (node (ref "IC1") (pin "8") (pinfunction "VCAP_8") (pintype "power_in"))
    )
    (net (code "25") (name "Net-(IC4-DC)") (class "Default")
      (node (ref "IC4") (pin "1") (pinfunction "SWC_1") (pintype "passive"))
      (node (ref "IC4") (pin "7") (pinfunction "IS_7") (pintype "passive"))
      (node (ref "IC4") (pin "8") (pinfunction "DC_8") (pintype "passive"))
      (node (ref "R16") (pin "2") (pinfunction "2_2") (pintype "passive"))
    )
    (net (code "26") (name "Net-(IC4-FB)") (class "Default")
      (node (ref "IC4") (pin "5") (pinfunction "FB_5") (pintype "passive"))
      (node (ref "R17") (pin "1") (pinfunction "1_1") (pintype "passive"))
      (node (ref "R18") (pin "2") (pinfunction "2_2") (pintype "passive"))
    )
    (net (code "27") (name "Net-(IC4-SWE)") (class "Default")
      (node (ref "IC4") (pin "2") (pinfunction "SWE_2") (pintype "passive"))
      (node (ref "L3") (pin "1") (pinfunction "1_1") (pintype "passive"))
      (node (ref "U$16") (pin "C") (pinfunction "C_C") (pintype "passive"))
    )
    (net (code "28") (name "Net-(IC4-TC)") (class "Default")
      (node (ref "C15") (pin "2") (pinfunction "2_2") (pintype "passive"))
      (node (ref "IC4") (pin "3") (pinfunction "TC_3") (pintype "passive"))
    )
    (net (code "29") (name "Net-(IC6-VI)") (class "Default")
      (node (ref "IC6") (pin "1") (pinfunction "VI_1") (pintype "input"))
      (node (ref "L3") (pin "2") (pinfunction "2_2") (pintype "passive"))
      (node (ref "R17") (pin "2") (pinfunction "2_2") (pintype "passive"))
      (node (ref "U$17") (pin "P$1") (pinfunction "+_P$1") (pintype "passive"))
    )
    (net (code "30") (name "Net-(LOAD1A-KL)") (class "Default")
      (node (ref "LOAD1") (pin "1") (pinfunction "KL_1") (pintype "passive"))
      (node (ref "R6") (pin "2") (pinfunction "2_2") (pintype "passive"))
      (node (ref "T2") (pin "T1") (pinfunction "A1_T1") (pintype "passive"))
    )
    (net (code "31") (name "Net-(LOADA-KL)") (class "Default")
      (node (ref "LOAD") (pin "1") (pinfunction "KL_1") (pintype "passive"))
      (node (ref "R2") (pin "1") (pinfunction "1_1") (pintype "passive"))
      (node (ref "T1") (pin "T1") (pinfunction "A1_T1") (pintype "passive"))
    )
    (net (code "32") (name "Net-(OK1-A)") (class "Default")
      (node (ref "OK1") (pin "1") (pinfunction "A_1") (pintype "passive"))
      (node (ref "R3") (pin "1") (pinfunction "1_1") (pintype "passive"))
    )
    (net (code "33") (name "Net-(OK1-A1)") (class "Default")
      (node (ref "OK1") (pin "4") (pinfunction "A1_4") (pintype "passive"))
      (node (ref "R2") (pin "2") (pinfunction "2_2") (pintype "passive"))
      (node (ref "T1") (pin "G") (pinfunction "G_G") (pintype "passive"))
    )
    (net (code "34") (name "Net-(OK1-A2)") (class "Default")
      (node (ref "OK1") (pin "6") (pinfunction "A2_6") (pintype "passive"))
      (node (ref "R1") (pin "1") (pinfunction "1_1") (pintype "passive"))
    )
    (net (code "35") (name "Net-(OK2-A)") (class "Default")
      (node (ref "OK2") (pin "1") (pinfunction "A_1") (pintype "passive"))
      (node (ref "R7") (pin "1") (pinfunction "1_1") (pintype "passive"))
    )
    (net (code "36") (name "Net-(OK2-A1)") (class "Default")
      (node (ref "OK2") (pin "4") (pinfunction "A1_4") (pintype "passive"))
      (node (ref "R6") (pin "1") (pinfunction "1_1") (pintype "passive"))
      (node (ref "T2") (pin "G") (pinfunction "G_G") (pintype "passive"))
    )
    (net (code "37") (name "Net-(OK2-A2)") (class "Default")
      (node (ref "OK2") (pin "6") (pinfunction "A2_6") (pintype "passive"))
      (node (ref "R5") (pin "2") (pinfunction "2_2") (pintype "passive"))
    )
    (net (code "38") (name "Net-(OK3-A)") (class "Default")
      (node (ref "OK3") (pin "1") (pinfunction "A_1") (pintype "passive"))
      (node (ref "R30") (pin "2") (pinfunction "2_2") (pintype "passive"))
    )
    (net (code "39") (name "Net-(OK3-C)") (class "Default")
      (node (ref "OK3") (pin "2") (pinfunction "C_2") (pintype "passive"))
      (node (ref "U$30") (pin "3") (pinfunction "D_3") (pintype "passive"))
    )
    (net (code "40") (name "Net-(OK3-COL)") (class "Default")
      (node (ref "OK3") (pin "4") (pinfunction "COL_4") (pintype "passive"))
      (node (ref "R25") (pin "2") (pinfunction "2_2") (pintype "passive"))
      (node (ref "R27") (pin "2") (pinfunction "2_2") (pintype "passive"))
    )
    (net (code "41") (name "Net-(OK3-EMIT)") (class "Default")
      (node (ref "OK3") (pin "3") (pinfunction "EMIT_3") (pintype "passive"))
      (node (ref "R15") (pin "2") (pinfunction "2_2") (pintype "passive"))
      (node (ref "R26") (pin "2") (pinfunction "2_2") (pintype "passive"))
    )
    (net (code "42") (name "Net-(OK4-A)") (class "Default")
      (node (ref "OK4") (pin "1") (pinfunction "A_1") (pintype "passive"))
      (node (ref "R28") (pin "1") (pinfunction "1_1") (pintype "passive"))
    )
    (net (code "43") (name "Net-(OK4-C)") (class "Default")
      (node (ref "OK4") (pin "2") (pinfunction "C_2") (pintype "passive"))
      (node (ref "U$28") (pin "3") (pinfunction "D_3") (pintype "passive"))
    )
    (net (code "44") (name "Net-(OK4-COL)") (class "Default")
      (node (ref "OK4") (pin "4") (pinfunction "COL_4") (pintype "passive"))
      (node (ref "R19") (pin "2") (pinfunction "2_2") (pintype "passive"))
      (node (ref "R23") (pin "2") (pinfunction "2_2") (pintype "passive"))
    )
    (net (code "45") (name "Net-(OK4-EMIT)") (class "Default")
      (node (ref "OK4") (pin "3") (pinfunction "EMIT_3") (pintype "passive"))
      (node (ref "R22") (pin "2") (pinfunction "2_2") (pintype "passive"))
      (node (ref "R9") (pin "1") (pinfunction "1_1") (pintype "passive"))
    )
    (net (code "46") (name "Net-(OK5-A)") (class "Default")
      (node (ref "OK5") (pin "1") (pinfunction "A_1") (pintype "passive"))
      (node (ref "R29") (pin "1") (pinfunction "1_1") (pintype "passive"))
    )
    (net (code "47") (name "Net-(OK5-C)") (class "Default")
      (node (ref "OK5") (pin "2") (pinfunction "C_2") (pintype "passive"))
      (node (ref "U$29") (pin "3") (pinfunction "D_3") (pintype "passive"))
    )
    (net (code "48") (name "Net-(OK5-COL)") (class "Default")
      (node (ref "OK5") (pin "4") (pinfunction "COL_4") (pintype "passive"))
      (node (ref "R20") (pin "2") (pinfunction "2_2") (pintype "passive"))
      (node (ref "R24") (pin "2") (pinfunction "2_2") (pintype "passive"))
    )
    (net (code "49") (name "Net-(OK5-EMIT)") (class "Default")
      (node (ref "OK5") (pin "3") (pinfunction "EMIT_3") (pintype "passive"))
      (node (ref "R21") (pin "2") (pinfunction "2_2") (pintype "passive"))
      (node (ref "R8") (pin "1") (pinfunction "1_1") (pintype "passive"))
    )
    (net (code "50") (name "Net-(R4-Pad2)") (class "Default")
      (node (ref "R4") (pin "2") (pinfunction "2_2") (pintype "passive"))
      (node (ref "U$2") (pin "A") (pinfunction "A_A") (pintype "passive"))
    )
    (net (code "51") (name "Net-(R14-Pad2)") (class "Default")
      (node (ref "R14") (pin "2") (pinfunction "2_2") (pintype "passive"))
      (node (ref "U$5") (pin "A") (pinfunction "A_A") (pintype "passive"))
    )
    (net (code "52") (name "Net-(U$1-G)") (class "Default")
      (node (ref "100") (pin "2") (pinfunction "2_2") (pintype "passive"))
      (node (ref "10K") (pin "2") (pinfunction "2_2") (pintype "passive"))
      (node (ref "U$1") (pin "1") (pinfunction "G_1") (pintype "passive"))
    )
    (net (code "53") (name "Net-(U$4-RO)") (class "Default")
      (node (ref "R31") (pin "1") (pinfunction "1_1") (pintype "passive"))
      (node (ref "U$4") (pin "1") (pinfunction "RO_1") (pintype "bidirectional"))
    )
    (net (code "54") (name "Net-(U$7-P0)") (class "Default")
      (node (ref "JP4") (pin "4") (pinfunction "4_4") (pintype "passive"))
      (node (ref "U$7") (pin "4") (pinfunction "P0_4") (pintype "bidirectional"))
    )
    (net (code "55") (name "Net-(U$7-P1)") (class "Default")
      (node (ref "JP4") (pin "3") (pinfunction "3_3") (pintype "passive"))
      (node (ref "U$7") (pin "5") (pinfunction "P1_5") (pintype "bidirectional"))
    )
    (net (code "56") (name "Net-(U$7-P2)") (class "Default")
      (node (ref "JP4") (pin "2") (pinfunction "2_2") (pintype "passive"))
      (node (ref "U$7") (pin "6") (pinfunction "P2_6") (pintype "bidirectional"))
    )
    (net (code "57") (name "Net-(U$7-P3)") (class "Default")
      (node (ref "JP4") (pin "1") (pinfunction "1_1") (pintype "passive"))
      (node (ref "U$7") (pin "7") (pinfunction "P3_7") (pintype "bidirectional"))
    )
    (net (code "58") (name "Net-(U$7-P4)") (class "Default")
      (node (ref "JP4") (pin "8") (pinfunction "8_8") (pintype "passive"))
      (node (ref "U$7") (pin "9") (pinfunction "P4_9") (pintype "bidirectional"))
    )
    (net (code "59") (name "Net-(U$7-P5)") (class "Default")
      (node (ref "JP4") (pin "7") (pinfunction "7_7") (pintype "passive"))
      (node (ref "U$7") (pin "10") (pinfunction "P5_10") (pintype "bidirectional"))
    )
    (net (code "60") (name "Net-(U$7-P6)") (class "Default")
      (node (ref "JP4") (pin "6") (pinfunction "6_6") (pintype "passive"))
      (node (ref "U$7") (pin "11") (pinfunction "P6_11") (pintype "bidirectional"))
    )
    (net (code "61") (name "Net-(U$7-P7)") (class "Default")
      (node (ref "JP4") (pin "5") (pinfunction "5_5") (pintype "passive"))
      (node (ref "U$7") (pin "12") (pinfunction "P7_12") (pintype "bidirectional"))
    )
    (net (code "62") (name "Net-(U$13-D)") (class "Default")
      (node (ref "R11") (pin "2") (pinfunction "2_2") (pintype "passive"))
      (node (ref "U$13") (pin "3") (pinfunction "D_3") (pintype "passive"))
      (node (ref "U$4") (pin "4") (pinfunction "DI_4") (pintype "bidirectional"))
    )
    (net (code "63") (name "Net-(U$13-G)") (class "Default")
      (node (ref "R22") (pin "1") (pinfunction "1_1") (pintype "passive"))
      (node (ref "R23") (pin "1") (pinfunction "1_1") (pintype "passive"))
      (node (ref "U$13") (pin "1") (pinfunction "G_1") (pintype "passive"))
    )
    (net (code "64") (name "Net-(U$14-D)") (class "Default")
      (node (ref "R10") (pin "2") (pinfunction "2_2") (pintype "passive"))
      (node (ref "U$14") (pin "3") (pinfunction "D_3") (pintype "passive"))
      (node (ref "U$4") (pin "2") (pinfunction "~{RE}_2") (pintype "bidirectional"))
    )
    (net (code "65") (name "Net-(U$14-G)") (class "Default")
      (node (ref "R21") (pin "1") (pinfunction "1_1") (pintype "passive"))
      (node (ref "R24") (pin "1") (pinfunction "1_1") (pintype "passive"))
      (node (ref "U$14") (pin "1") (pinfunction "G_1") (pintype "passive"))
    )
    (net (code "66") (name "Net-(U$15-G)") (class "Default")
      (node (ref "R26") (pin "1") (pinfunction "1_1") (pintype "passive"))
      (node (ref "R27") (pin "1") (pinfunction "1_1") (pintype "passive"))
      (node (ref "U$15") (pin "1") (pinfunction "G_1") (pintype "passive"))
    )
    (net (code "67") (name "Net-(U$28-G)") (class "Default")
      (node (ref "R34") (pin "1") (pinfunction "1_1") (pintype "passive"))
      (node (ref "R37") (pin "2") (pinfunction "2_2") (pintype "passive"))
      (node (ref "U$28") (pin "1") (pinfunction "G_1") (pintype "passive"))
    )
    (net (code "68") (name "Net-(U$29-G)") (class "Default")
      (node (ref "R33") (pin "1") (pinfunction "1_1") (pintype "passive"))
      (node (ref "R36") (pin "2") (pinfunction "2_2") (pintype "passive"))
      (node (ref "U$29") (pin "1") (pinfunction "G_1") (pintype "passive"))
    )
    (net (code "69") (name "Net-(U$30-G)") (class "Default")
      (node (ref "R31") (pin "2") (pinfunction "2_2") (pintype "passive"))
      (node (ref "R35") (pin "1") (pinfunction "1_1") (pintype "passive"))
      (node (ref "U$30") (pin "1") (pinfunction "G_1") (pintype "passive"))
    )
    (net (code "70") (name "PWM") (class "Default")
      (node (ref "100") (pin "1") (pinfunction "1_1") (pintype "passive"))
      (node (ref "IC1") (pin "20") (pinfunction "PD3/AIN4/TIM2_CH2/ADC_ETR_20") (pintype "bidirectional"))
    )
    (net (code "71") (name "RS485_A") (class "Default")
      (node (ref "+RS485-") (pin "1") (pinfunction "KL_1") (pintype "passive"))
      (node (ref "R32") (pin "1") (pinfunction "1_1") (pintype "passive"))
      (node (ref "U$4") (pin "6") (pinfunction "A_6") (pintype "bidirectional"))
    )
    (net (code "72") (name "RS485_B") (class "Default")
      (node (ref "+RS485-") (pin "2") (pinfunction "KL_2") (pintype "passive"))
      (node (ref "R32") (pin "2") (pinfunction "2_2") (pintype "passive"))
      (node (ref "U$4") (pin "7") (pinfunction "B_7") (pintype "bidirectional"))
    )
    (net (code "73") (name "RS485_DIR") (class "Default")
      (node (ref "IC2") (pin "29") (pinfunction "PA8_29") (pintype "bidirectional"))
      (node (ref "R36") (pin "1") (pinfunction "1_1") (pintype "passive"))
    )
    (net (code "74") (name "RS485_RX") (class "Default")
      (node (ref "IC2") (pin "31") (pinfunction "PA10_31") (pintype "bidirectional"))
      (node (ref "R12") (pin "2") (pinfunction "2_2") (pintype "passive"))
      (node (ref "R41") (pin "1") (pinfunction "1_1") (pintype "passive"))
      (node (ref "U$15") (pin "3") (pinfunction "D_3") (pintype "passive"))
    )
    (net (code "75") (name "RS485_TX") (class "Default")
      (node (ref "IC2") (pin "30") (pinfunction "PA9_30") (pintype "bidirectional"))
      (node (ref "R37") (pin "1") (pinfunction "1_1") (pintype "passive"))
    )
    (net (code "76") (name "SCL") (class "Default")
      (node (ref "006") (pin "2") (pinfunction "2_2") (pintype "passive"))
      (node (ref "IC2") (pin "22") (pinfunction "PB11_22") (pintype "bidirectional"))
      (node (ref "U$7") (pin "14") (pinfunction "SCL_14") (pintype "input"))
    )
    (net (code "77") (name "SDA") (class "Default")
      (node (ref "005") (pin "2") (pinfunction "2_2") (pintype "passive"))
      (node (ref "IC2") (pin "21") (pinfunction "PB10_21") (pintype "bidirectional"))
      (node (ref "U$7") (pin "15") (pinfunction "SDA_15") (pintype "bidirectional"))
    )
    (net (code "78") (name "SPI_MISO") (class "Default")
      (node (ref "IC2") (pin "27") (pinfunction "PB14_27") (pintype "bidirectional"))
      (node (ref "JP4") (pin "12") (pinfunction "12_12") (pintype "passive"))
    )
    (net (code "79") (name "SPI_MOSI") (class "Default")
      (node (ref "IC2") (pin "28") (pinfunction "PB15_28") (pintype "bidirectional"))
      (node (ref "JP4") (pin "14") (pinfunction "14_14") (pintype "passive"))
    )
    (net (code "80") (name "SPI_SCK") (class "Default")
      (node (ref "IC2") (pin "26") (pinfunction "PB13_26") (pintype "bidirectional"))
      (node (ref "JP4") (pin "10") (pinfunction "10_10") (pintype "passive"))
    )
    (net (code "81") (name "STM8_SWIM") (class "Default")
      (node (ref "IC1") (pin "18") (pinfunction "PD1/SWIM_18") (pintype "bidirectional"))
      (node (ref "JP2") (pin "3") (pinfunction "3_3") (pintype "passive"))
    )
    (net (code "82") (name "STM8_~{RST}") (class "Default")
      (node (ref "IC1") (pin "4") (pinfunction "~{RST}_4") (pintype "input"))
      (node (ref "JP2") (pin "1") (pinfunction "1_1") (pintype "passive"))
      (node (ref "R13") (pin "2") (pinfunction "2_2") (pintype "passive"))
    )
    (net (code "83") (name "STM32_RX") (class "Default")
      (node (ref "IC2") (pin "13") (pinfunction "PA3_13") (pintype "bidirectional"))
      (node (ref "R38") (pin "2") (pinfunction "2_2") (pintype "passive"))
      (node (ref "R39") (pin "1") (pinfunction "1_1") (pintype "passive"))
    )
    (net (code "84") (name "STM32_TX") (class "Default")
      (node (ref "IC2") (pin "12") (pinfunction "PA2_12") (pintype "bidirectional"))
      (node (ref "R40") (pin "2") (pinfunction "2_2") (pintype "passive"))
    )
    (net (code "85") (name "SWCLK") (class "Default")
      (node (ref "IC2") (pin "37") (pinfunction "PA14_37") (pintype "bidirectional"))
      (node (ref "JP1") (pin "3") (pinfunction "3_3") (pintype "passive"))
    )
    (net (code "86") (name "SWDIO") (class "Default")
      (node (ref "IC2") (pin "34") (pinfunction "PA13_34") (pintype "bidirectional"))
      (node (ref "JP1") (pin "2") (pinfunction "2_2") (pintype "passive"))
    )
    (net (code "87") (name "unconnected-(001-Pad1)") (class "Default")
      (node (ref "001") (pin "1") (pinfunction "1_1") (pintype "passive"))
    )
    (net (code "88") (name "unconnected-(001-Pad2)") (class "Default")
      (node (ref "001") (pin "2") (pinfunction "2_2") (pintype "passive"))
    )
    (net (code "89") (name "unconnected-(IC1-OSCIN{slash}PA1-Pad5)") (class "Default")
      (node (ref "IC1") (pin "5") (pinfunction "OSCIN/PA1_5") (pintype "bidirectional"))
    )
    (net (code "90") (name "unconnected-(IC1-OSCOUT{slash}PA2-Pad6)") (class "Default")
      (node (ref "IC1") (pin "6") (pinfunction "OSCOUT/PA2_6") (pintype "bidirectional"))
    )
    (net (code "91") (name "unconnected-(IC1-PC3{slash}TIM1_CH3{slash}[TLI]{slash}[~{TIM1_CH1}]-Pad13)") (class "Default")
      (node (ref "IC1") (pin "13") (pinfunction "PC3/TIM1_CH3/[TLI]/[~{TIM1_CH1}]_13") (pintype "bidirectional"))
    )
    (net (code "92") (name "unconnected-(IC1-PC6{slash}SPI_MOSI{slash}[TIM1_CH1]-Pad16)") (class "Default")
      (node (ref "IC1") (pin "16") (pinfunction "PC6/SPI_MOSI/[TIM1_CH1]_16") (pintype "bidirectional"))
    )
    (net (code "93") (name "unconnected-(IC2A-OSC_IN-Pad5)") (class "Default")
      (node (ref "IC2") (pin "5") (pinfunction "OSC_IN_5") (pintype "bidirectional"))
    )
    (net (code "94") (name "unconnected-(IC2A-OSC_OUT-Pad6)") (class "Default")
      (node (ref "IC2") (pin "6") (pinfunction "OSC_OUT_6") (pintype "bidirectional"))
    )
    (net (code "95") (name "unconnected-(IC2A-PA0-WKUP-Pad10)") (class "Default")
      (node (ref "IC2") (pin "10") (pinfunction "PA0-WKUP_10") (pintype "bidirectional"))
    )
    (net (code "96") (name "unconnected-(IC2A-PA1-Pad11)") (class "Default")
      (node (ref "IC2") (pin "11") (pinfunction "PA1_11") (pintype "bidirectional"))
    )
    (net (code "97") (name "unconnected-(IC2A-PA4-Pad14)") (class "Default")
      (node (ref "IC2") (pin "14") (pinfunction "PA4_14") (pintype "bidirectional"))
    )
    (net (code "98") (name "unconnected-(IC2A-PA5-Pad15)") (class "Default")
      (node (ref "IC2") (pin "15") (pinfunction "PA5_15") (pintype "bidirectional"))
    )
    (net (code "99") (name "unconnected-(IC2A-PA6-Pad16)") (class "Default")
      (node (ref "IC2") (pin "16") (pinfunction "PA6_16") (pintype "bidirectional"))
    )
    (net (code "100") (name "unconnected-(IC2A-PA7-Pad17)") (class "Default")
      (node (ref "IC2") (pin "17") (pinfunction "PA7_17") (pintype "bidirectional"))
    )
    (net (code "101") (name "unconnected-(IC2A-PA15-Pad38)") (class "Default")
      (node (ref "IC2") (pin "38") (pinfunction "PA15_38") (pintype "bidirectional"))
    )
    (net (code "102") (name "unconnected-(IC2A-PB0-Pad18)") (class "Default")
      (node (ref "IC2") (pin "18") (pinfunction "PB0_18") (pintype "bidirectional"))
    )
    (net (code "103") (name "unconnected-(IC2A-PB1-Pad19)") (class "Default")
      (node (ref "IC2") (pin "19") (pinfunction "PB1_19") (pintype "bidirectional"))
    )
    (net (code "104") (name "unconnected-(IC2A-PB2-Pad20)") (class "Default")
      (node (ref "IC2") (pin "20") (pinfunction "PB2_20") (pintype "bidirectional"))
    )
    (net (code "105") (name "unconnected-(IC2A-PB3-Pad39)") (class "Default")
      (node (ref "IC2") (pin "39") (pinfunction "PB3_39") (pintype "bidirectional"))
    )
    (net (code "106") (name "unconnected-(IC2A-PB4-Pad40)") (class "Default")
      (node (ref "IC2") (pin "40") (pinfunction "PB4_40") (pintype "bidirectional"))
    )
    (net (code "107") (name "unconnected-(IC2A-PB5-Pad41)") (class "Default")
      (node (ref "IC2") (pin "41") (pinfunction "PB5_41") (pintype "bidirectional"))
    )
    (net (code "108") (name "unconnected-(IC2A-PB6-Pad42)") (class "Default")
      (node (ref "IC2") (pin "42") (pinfunction "PB6_42") (pintype "bidirectional"))
    )
    (net (code "109") (name "unconnected-(IC2A-PB7-Pad43)") (class "Default")
      (node (ref "IC2") (pin "43") (pinfunction "PB7_43") (pintype "bidirectional"))
    )
    (net (code "110") (name "unconnected-(IC2A-PB8-Pad45)") (class "Default")
      (node (ref "IC2") (pin "45") (pinfunction "PB8_45") (pintype "bidirectional"))
    )
    (net (code "111") (name "unconnected-(IC2A-PB9-Pad46)") (class "Default")
      (node (ref "IC2") (pin "46") (pinfunction "PB9_46") (pintype "bidirectional"))
    )
    (net (code "112") (name "unconnected-(IC2A-PB12-Pad25)") (class "Default")
      (node (ref "IC2") (pin "25") (pinfunction "PB12_25") (pintype "bidirectional"))
    )
    (net (code "113") (name "unconnected-(IC2A-PC13-Pad2)") (class "Default")
      (node (ref "IC2") (pin "2") (pinfunction "PC13_2") (pintype "bidirectional"))
    )
    (net (code "114") (name "unconnected-(IC2A-PC14-Pad3)") (class "Default")
      (node (ref "IC2") (pin "3") (pinfunction "PC14_3") (pintype "bidirectional"))
    )
    (net (code "115") (name "unconnected-(IC2A-PC15-Pad4)") (class "Default")
      (node (ref "IC2") (pin "4") (pinfunction "PC15_4") (pintype "bidirectional"))
    )
    (net (code "116") (name "unconnected-(U$7-~{INT}-Pad13)") (class "Default")
      (node (ref "U$7") (pin "13") (pinfunction "~{INT}_13") (pintype "output"))
    )
    (net (code "117") (name "unconnected-(U$22-PadP$1)") (class "Default")
      (node (ref "U$22") (pin "P$1") (pinfunction "P$1_P$1") (pintype "bidirectional"))
    )
    (net (code "118") (name "unconnected-(U$22-PadP$2)") (class "Default")
      (node (ref "U$22") (pin "P$2") (pinfunction "P$2_P$2") (pintype "bidirectional"))
    )
    (net (code "119") (name "unconnected-(U$22-PadP$3)") (class "Default")
      (node (ref "U$22") (pin "P$3") (pinfunction "P$3_P$3") (pintype "bidirectional"))
    )
    (net (code "120") (name "unconnected-(U$22-PadP$4)") (class "Default")
      (node (ref "U$22") (pin "P$4") (pinfunction "P$4_P$4") (pintype "bidirectional"))
    )
    (net (code "121") (name "unconnected-(U$22-PadP$5)") (class "Default")
      (node (ref "U$22") (pin "P$5") (pinfunction "P$5_P$5") (pintype "bidirectional"))
    )
    (net (code "122") (name "unconnected-(U$22-PadP$6)") (class "Default")
      (node (ref "U$22") (pin "P$6") (pinfunction "P$6_P$6") (pintype "bidirectional"))
    )
    (net (code "123") (name "unconnected-(U$22-PadP$7)") (class "Default")
      (node (ref "U$22") (pin "P$7") (pinfunction "P$7_P$7") (pintype "bidirectional"))
    )
    (net (code "124") (name "unconnected-(U$22-PadP$8)") (class "Default")
      (node (ref "U$22") (pin "P$8") (pinfunction "P$8_P$8") (pintype "bidirectional"))
    )
    (net (code "125") (name "unconnected-(U$22-PadP$9)") (class "Default")
      (node (ref "U$22") (pin "P$9") (pinfunction "P$9_P$9") (pintype "bidirectional"))
    )
    (net (code "126") (name "unconnected-(U$23-PadP$1)") (class "Default")
      (node (ref "U$23") (pin "P$1") (pinfunction "P$1_P$1") (pintype "bidirectional"))
    )
    (net (code "127") (name "unconnected-(U$23-PadP$2)") (class "Default")
      (node (ref "U$23") (pin "P$2") (pinfunction "P$2_P$2") (pintype "bidirectional"))
    )
    (net (code "128") (name "unconnected-(U$23-PadP$3)") (class "Default")
      (node (ref "U$23") (pin "P$3") (pinfunction "P$3_P$3") (pintype "bidirectional"))
    )
    (net (code "129") (name "unconnected-(U$23-PadP$4)") (class "Default")
      (node (ref "U$23") (pin "P$4") (pinfunction "P$4_P$4") (pintype "bidirectional"))
    )
    (net (code "130") (name "unconnected-(U$23-PadP$5)") (class "Default")
      (node (ref "U$23") (pin "P$5") (pinfunction "P$5_P$5") (pintype "bidirectional"))
    )
    (net (code "131") (name "unconnected-(U$23-PadP$6)") (class "Default")
      (node (ref "U$23") (pin "P$6") (pinfunction "P$6_P$6") (pintype "bidirectional"))
    )
    (net (code "132") (name "unconnected-(U$23-PadP$7)") (class "Default")
      (node (ref "U$23") (pin "P$7") (pinfunction "P$7_P$7") (pintype "bidirectional"))
    )
    (net (code "133") (name "unconnected-(U$23-PadP$8)") (class "Default")
      (node (ref "U$23") (pin "P$8") (pinfunction "P$8_P$8") (pintype "bidirectional"))
    )
    (net (code "134") (name "unconnected-(U$23-PadP$9)") (class "Default")
      (node (ref "U$23") (pin "P$9") (pinfunction "P$9_P$9") (pintype "bidirectional"))
    )
    (net (code "135") (name "unconnected-(U$24-PadP$1)") (class "Default")
      (node (ref "U$24") (pin "P$1") (pinfunction "P$1_P$1") (pintype "bidirectional"))
    )
    (net (code "136") (name "unconnected-(U$24-PadP$2)") (class "Default")
      (node (ref "U$24") (pin "P$2") (pinfunction "P$2_P$2") (pintype "bidirectional"))
    )
    (net (code "137") (name "unconnected-(U$24-PadP$3)") (class "Default")
      (node (ref "U$24") (pin "P$3") (pinfunction "P$3_P$3") (pintype "bidirectional"))
    )
    (net (code "138") (name "unconnected-(U$24-PadP$4)") (class "Default")
      (node (ref "U$24") (pin "P$4") (pinfunction "P$4_P$4") (pintype "bidirectional"))
    )
    (net (code "139") (name "unconnected-(U$24-PadP$5)") (class "Default")
      (node (ref "U$24") (pin "P$5") (pinfunction "P$5_P$5") (pintype "bidirectional"))
    )
    (net (code "140") (name "unconnected-(U$24-PadP$6)") (class "Default")
      (node (ref "U$24") (pin "P$6") (pinfunction "P$6_P$6") (pintype "bidirectional"))
    )
    (net (code "141") (name "unconnected-(U$24-PadP$7)") (class "Default")
      (node (ref "U$24") (pin "P$7") (pinfunction "P$7_P$7") (pintype "bidirectional"))
    )
    (net (code "142") (name "unconnected-(U$24-PadP$8)") (class "Default")
      (node (ref "U$24") (pin "P$8") (pinfunction "P$8_P$8") (pintype "bidirectional"))
    )
    (net (code "143") (name "unconnected-(U$24-PadP$9)") (class "Default")
      (node (ref "U$24") (pin "P$9") (pinfunction "P$9_P$9") (pintype "bidirectional"))
    )
    (net (code "144") (name "unconnected-(U$25-PadP$1)") (class "Default")
      (node (ref "U$25") (pin "P$1") (pinfunction "P$1_P$1") (pintype "bidirectional"))
    )
    (net (code "145") (name "unconnected-(U$25-PadP$2)") (class "Default")
      (node (ref "U$25") (pin "P$2") (pinfunction "P$2_P$2") (pintype "bidirectional"))
    )
    (net (code "146") (name "unconnected-(U$25-PadP$3)") (class "Default")
      (node (ref "U$25") (pin "P$3") (pinfunction "P$3_P$3") (pintype "bidirectional"))
    )
    (net (code "147") (name "unconnected-(U$25-PadP$4)") (class "Default")
      (node (ref "U$25") (pin "P$4") (pinfunction "P$4_P$4") (pintype "bidirectional"))
    )
    (net (code "148") (name "unconnected-(U$25-PadP$5)") (class "Default")
      (node (ref "U$25") (pin "P$5") (pinfunction "P$5_P$5") (pintype "bidirectional"))
    )
    (net (code "149") (name "unconnected-(U$25-PadP$6)") (class "Default")
      (node (ref "U$25") (pin "P$6") (pinfunction "P$6_P$6") (pintype "bidirectional"))
    )
    (net (code "150") (name "unconnected-(U$25-PadP$7)") (class "Default")
      (node (ref "U$25") (pin "P$7") (pinfunction "P$7_P$7") (pintype "bidirectional"))
    )
    (net (code "151") (name "unconnected-(U$25-PadP$8)") (class "Default")
      (node (ref "U$25") (pin "P$8") (pinfunction "P$8_P$8") (pintype "bidirectional"))
    )
    (net (code "152") (name "unconnected-(U$25-PadP$9)") (class "Default")
      (node (ref "U$25") (pin "P$9") (pinfunction "P$9_P$9") (pintype "bidirectional"))
    )
    (net (code "153") (name "unconnected-(U$26-PadP$1)") (class "Default")
      (node (ref "U$26") (pin "P$1") (pinfunction "P$1_P$1") (pintype "bidirectional"))
    )
    (net (code "154") (name "unconnected-(U$26-PadP$2)") (class "Default")
      (node (ref "U$26") (pin "P$2") (pinfunction "P$2_P$2") (pintype "bidirectional"))
    )
    (net (code "155") (name "unconnected-(U$26-PadP$3)") (class "Default")
      (node (ref "U$26") (pin "P$3") (pinfunction "P$3_P$3") (pintype "bidirectional"))
    )
    (net (code "156") (name "unconnected-(U$26-PadP$4)") (class "Default")
      (node (ref "U$26") (pin "P$4") (pinfunction "P$4_P$4") (pintype "bidirectional"))
    )
    (net (code "157") (name "unconnected-(U$26-PadP$5)") (class "Default")
      (node (ref "U$26") (pin "P$5") (pinfunction "P$5_P$5") (pintype "bidirectional"))
    )
    (net (code "158") (name "unconnected-(U$26-PadP$6)") (class "Default")
      (node (ref "U$26") (pin "P$6") (pinfunction "P$6_P$6") (pintype "bidirectional"))
    )
    (net (code "159") (name "unconnected-(U$26-PadP$7)") (class "Default")
      (node (ref "U$26") (pin "P$7") (pinfunction "P$7_P$7") (pintype "bidirectional"))
    )
    (net (code "160") (name "unconnected-(U$26-PadP$8)") (class "Default")
      (node (ref "U$26") (pin "P$8") (pinfunction "P$8_P$8") (pintype "bidirectional"))
    )
    (net (code "161") (name "unconnected-(U$26-PadP$9)") (class "Default")
      (node (ref "U$26") (pin "P$9") (pinfunction "P$9_P$9") (pintype "bidirectional"))
    )
    (net (code "162") (name "unconnected-(U$27-PadP$1)") (class "Default")
      (node (ref "U$27") (pin "P$1") (pinfunction "P$1_P$1") (pintype "bidirectional"))
    )
    (net (code "163") (name "unconnected-(U$27-PadP$2)") (class "Default")
      (node (ref "U$27") (pin "P$2") (pinfunction "P$2_P$2") (pintype "bidirectional"))
    )
    (net (code "164") (name "unconnected-(U$27-PadP$3)") (class "Default")
      (node (ref "U$27") (pin "P$3") (pinfunction "P$3_P$3") (pintype "bidirectional"))
    )
    (net (code "165") (name "unconnected-(U$27-PadP$4)") (class "Default")
      (node (ref "U$27") (pin "P$4") (pinfunction "P$4_P$4") (pintype "bidirectional"))
    )
    (net (code "166") (name "unconnected-(U$27-PadP$5)") (class "Default")
      (node (ref "U$27") (pin "P$5") (pinfunction "P$5_P$5") (pintype "bidirectional"))
    )
    (net (code "167") (name "unconnected-(U$27-PadP$6)") (class "Default")
      (node (ref "U$27") (pin "P$6") (pinfunction "P$6_P$6") (pintype "bidirectional"))
    )
    (net (code "168") (name "unconnected-(U$27-PadP$7)") (class "Default")
      (node (ref "U$27") (pin "P$7") (pinfunction "P$7_P$7") (pintype "bidirectional"))
    )
    (net (code "169") (name "unconnected-(U$27-PadP$8)") (class "Default")
      (node (ref "U$27") (pin "P$8") (pinfunction "P$8_P$8") (pintype "bidirectional"))
    )
    (net (code "170") (name "unconnected-(U$27-PadP$9)") (class "Default")
      (node (ref "U$27") (pin "P$9") (pinfunction "P$9_P$9") (pintype "bidirectional"))
    )
    (net (code "171") (name "~{RST}") (class "Default")
      (node (ref "004") (pin "2") (pinfunction "2_2") (pintype "passive"))
      (node (ref "IC2") (pin "7") (pinfunction "NRST_7") (pintype "bidirectional"))
      (node (ref "JP1") (pin "1") (pinfunction "1_1") (pintype "passive"))
    )
  )
)
